# CatCarousel.net
KiCad netlist of a schematic drawn in EAGLE
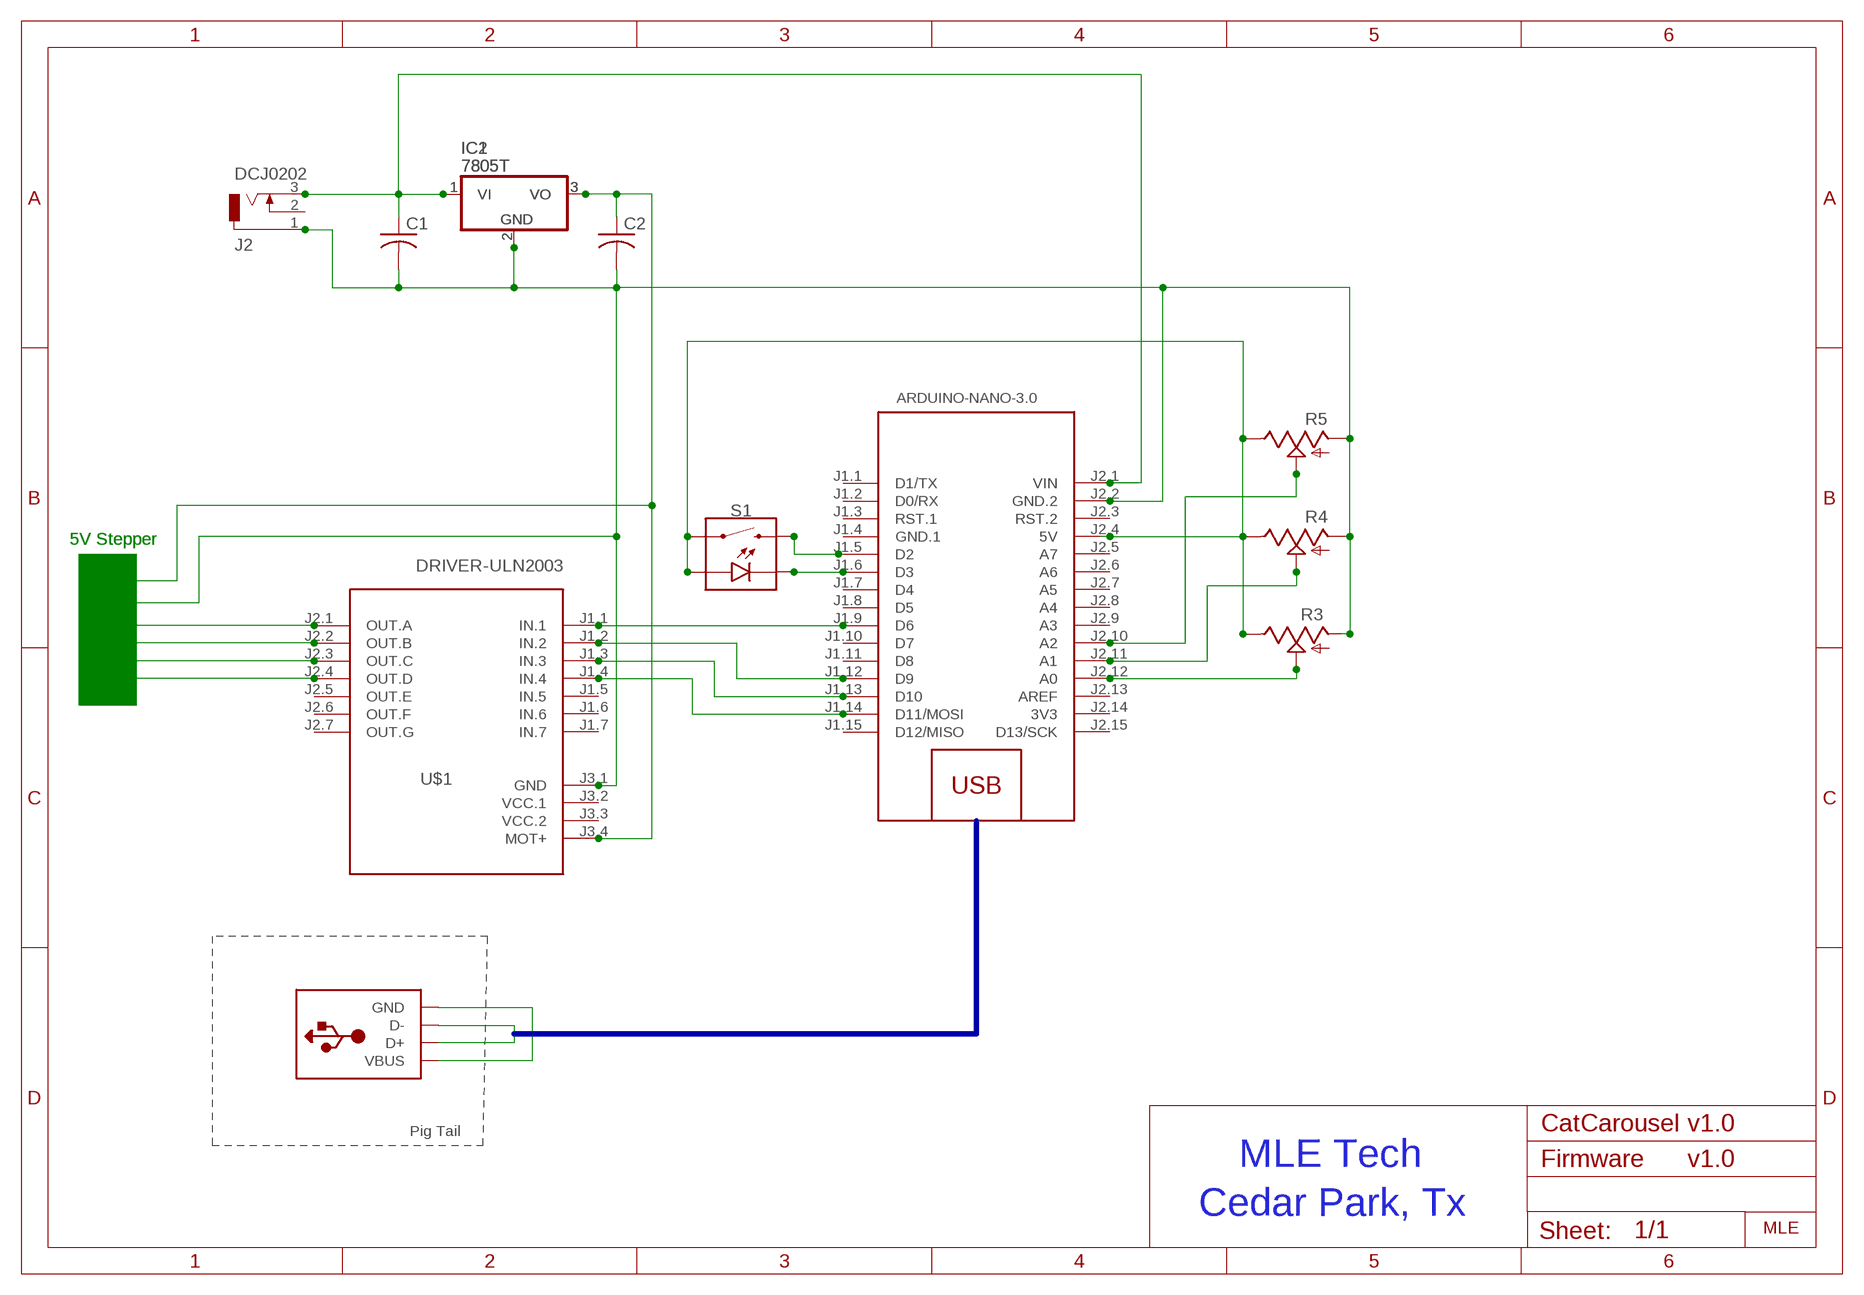
[diagram p0: schematic, sheet 1]

(export (version "E")
  (design (tool "Eeschema 10.0.6"))
  (components
    (comp (ref "C1")
      (value "C-US025-024X044")
      (footprint "eagle-import:C025-024X044")
      (libsource (lib "eagle-import") (part "C-US025-024X044"))
    )
    (comp (ref "C2")
      (value "C-US025-024X044")
      (footprint "eagle-import:C025-024X044")
      (libsource (lib "eagle-import") (part "C-US025-024X044"))
    )
    (comp (ref "IC1")
      (value "7805T")
      (footprint "eagle-import:TO220H")
      (libsource (lib "eagle-import") (part "78T05"))
    )
    (comp (ref "IC2")
      (value "7805T")
      (footprint "eagle-import:TO220H")
      (libsource (lib "eagle-import") (part "78T05"))
    )
    (comp (ref "J2")
      (value "DCJ0202")
      (footprint "eagle-import:DCJ0202")
      (libsource (lib "eagle-import") (part "DCJ0202"))
    )
    (comp (ref "M1")
      (value "ARDUINO-NANO-3.0")
      (footprint "eagle-import:ARDUINO-NANO-3.0")
      (libsource (lib "eagle-import") (part "ARDUINO-NANO-3.0"))
    )
    (comp (ref "R3")
      (value "TRIM_US-CA14H")
      (footprint "eagle-import:CA14H")
      (libsource (lib "eagle-import") (part "TRIM_US-CA14H"))
    )
    (comp (ref "R4")
      (value "TRIM_US-CA14H")
      (footprint "eagle-import:CA14H")
      (libsource (lib "eagle-import") (part "TRIM_US-CA14H"))
    )
    (comp (ref "R5")
      (value "TRIM_US-CA14H")
      (footprint "eagle-import:CA14H")
      (libsource (lib "eagle-import") (part "TRIM_US-CA14H"))
    )
    (comp (ref "S1")
      (value "MOMENTARY-SWITCH-SPST-LED-PTH-12MM")
      (footprint "eagle-import:TACTILE_SWITCH_LED_PTH_12MM")
      (libsource (lib "eagle-import") (part "MOMENTARY-SWITCH-SPST-LED-PTH-12MM"))
    )
    (comp (ref "U$1")
      (value "DRIVER-ULN2003")
      (footprint "eagle-import:DRIVER-ULN2003")
      (libsource (lib "eagle-import") (part "DRIVER-ULN2003"))
    )
    (comp (ref "X2")
      (value "USB-A")
      (footprint "eagle-import:MOLEX_480371000")
      (libsource (lib "eagle-import") (part "USB-A"))
    )
  )
  (nets
    (net (code "1") (name "/3V3") (class "Default")
      (node (ref "M1") (pin "J2.14") (pinfunction "3V3_J2.14") (pintype "power_in"))
    )
    (net (code "2") (name "/GND.1") (class "Default")
      (node (ref "M1") (pin "J1.4") (pinfunction "GND.1_J1.4") (pintype "power_in"))
    )
    (net (code "3") (name "/VCC.1") (class "Default")
      (node (ref "U$1") (pin "J3.2") (pinfunction "VCC.1_J3.2") (pintype "power_in"))
    )
    (net (code "4") (name "Net-(IC1-GND)") (class "Default")
      (node (ref "C1") (pin "2") (pinfunction "2_2") (pintype "passive"))
      (node (ref "C2") (pin "2") (pinfunction "2_2") (pintype "passive"))
      (node (ref "IC1") (pin "2") (pinfunction "GND_2") (pintype "passive"))
      (node (ref "IC2") (pin "2") (pinfunction "GND_2") (pintype "passive"))
      (node (ref "J2") (pin "1") (pinfunction "1_1") (pintype "passive"))
      (node (ref "M1") (pin "J2.2") (pinfunction "GND.2_J2.2") (pintype "power_in"))
      (node (ref "R3") (pin "A") (pinfunction "A_A") (pintype "passive"))
      (node (ref "R4") (pin "A") (pinfunction "A_A") (pintype "passive"))
      (node (ref "R5") (pin "A") (pinfunction "A_A") (pintype "passive"))
      (node (ref "U$1") (pin "J3.1") (pinfunction "GND_J3.1") (pintype "power_in"))
    )
    (net (code "5") (name "Net-(IC1-VI)") (class "Default")
      (node (ref "C1") (pin "1") (pinfunction "1_1") (pintype "passive"))
      (node (ref "IC1") (pin "1") (pinfunction "VI_1") (pintype "input"))
      (node (ref "IC2") (pin "1") (pinfunction "VI_1") (pintype "input"))
      (node (ref "J2") (pin "3") (pinfunction "3_3") (pintype "passive"))
      (node (ref "M1") (pin "J2.1") (pinfunction "VIN_J2.1") (pintype "power_in"))
    )
    (net (code "6") (name "Net-(IC1-VO)") (class "Default")
      (node (ref "C2") (pin "1") (pinfunction "1_1") (pintype "passive"))
      (node (ref "IC1") (pin "3") (pinfunction "VO_3") (pintype "passive"))
      (node (ref "IC2") (pin "3") (pinfunction "VO_3") (pintype "passive"))
      (node (ref "U$1") (pin "J3.4") (pinfunction "MOT+_J3.4") (pintype "bidirectional"))
    )
    (net (code "7") (name "Net-(M1-5V)") (class "Default")
      (node (ref "M1") (pin "J2.4") (pinfunction "5V_J2.4") (pintype "power_in"))
      (node (ref "R3") (pin "E") (pinfunction "E_E") (pintype "passive"))
      (node (ref "R4") (pin "E") (pinfunction "E_E") (pintype "passive"))
      (node (ref "R5") (pin "E") (pinfunction "E_E") (pintype "passive"))
      (node (ref "S1") (pin "4") (pinfunction "1_4") (pintype "passive"))
      (node (ref "S1") (pin "A") (pinfunction "A_A") (pintype "passive"))
    )
    (net (code "8") (name "Net-(M1-A0)") (class "Default")
      (node (ref "M1") (pin "J2.12") (pinfunction "A0_J2.12") (pintype "bidirectional"))
      (node (ref "R3") (pin "S") (pinfunction "S_S") (pintype "passive"))
    )
    (net (code "9") (name "Net-(M1-A1)") (class "Default")
      (node (ref "M1") (pin "J2.11") (pinfunction "A1_J2.11") (pintype "bidirectional"))
      (node (ref "R4") (pin "S") (pinfunction "S_S") (pintype "passive"))
    )
    (net (code "10") (name "Net-(M1-A2)") (class "Default")
      (node (ref "M1") (pin "J2.10") (pinfunction "A2_J2.10") (pintype "bidirectional"))
      (node (ref "R5") (pin "S") (pinfunction "S_S") (pintype "passive"))
    )
    (net (code "11") (name "Net-(M1-D2)") (class "Default")
      (node (ref "M1") (pin "J1.5") (pinfunction "D2_J1.5") (pintype "bidirectional"))
      (node (ref "S1") (pin "2") (pinfunction "2_2") (pintype "passive"))
    )
    (net (code "12") (name "Net-(M1-D3)") (class "Default")
      (node (ref "M1") (pin "J1.6") (pinfunction "D3_J1.6") (pintype "bidirectional"))
      (node (ref "S1") (pin "C") (pinfunction "C_C") (pintype "passive"))
    )
    (net (code "13") (name "Net-(M1-D6)") (class "Default")
      (node (ref "M1") (pin "J1.9") (pinfunction "D6_J1.9") (pintype "bidirectional"))
      (node (ref "U$1") (pin "J1.1") (pinfunction "IN.1_J1.1") (pintype "bidirectional"))
    )
    (net (code "14") (name "Net-(M1-D9)") (class "Default")
      (node (ref "M1") (pin "J1.12") (pinfunction "D9_J1.12") (pintype "bidirectional"))
      (node (ref "U$1") (pin "J1.2") (pinfunction "IN.2_J1.2") (pintype "bidirectional"))
    )
    (net (code "15") (name "Net-(M1-D10)") (class "Default")
      (node (ref "M1") (pin "J1.13") (pinfunction "D10_J1.13") (pintype "bidirectional"))
      (node (ref "U$1") (pin "J1.3") (pinfunction "IN.3_J1.3") (pintype "bidirectional"))
    )
    (net (code "16") (name "Net-(M1-D11{slash}MOSI)") (class "Default")
      (node (ref "M1") (pin "J1.14") (pinfunction "D11/MOSI_J1.14") (pintype "bidirectional"))
      (node (ref "U$1") (pin "J1.4") (pinfunction "IN.4_J1.4") (pintype "bidirectional"))
    )
    (net (code "17") (name "Net-(X2-D+)") (class "Default")
      (node (ref "X2") (pin "2") (pinfunction "D-_2") (pintype "bidirectional"))
      (node (ref "X2") (pin "3") (pinfunction "D+_3") (pintype "bidirectional"))
    )
    (net (code "18") (name "Net-(X2-GND)") (class "Default")
      (node (ref "X2") (pin "1") (pinfunction "VBUS_1") (pintype "power_in"))
      (node (ref "X2") (pin "4") (pinfunction "GND_4") (pintype "power_in"))
    )
    (net (code "19") (name "unconnected-(J2-Pad2)") (class "Default")
      (node (ref "J2") (pin "2") (pinfunction "2_2") (pintype "passive"))
    )
    (net (code "20") (name "unconnected-(M1-A3-PadJ2.9)") (class "Default")
      (node (ref "M1") (pin "J2.9") (pinfunction "A3_J2.9") (pintype "bidirectional"))
    )
    (net (code "21") (name "unconnected-(M1-A4-PadJ2.8)") (class "Default")
      (node (ref "M1") (pin "J2.8") (pinfunction "A4_J2.8") (pintype "bidirectional"))
    )
    (net (code "22") (name "unconnected-(M1-A5-PadJ2.7)") (class "Default")
      (node (ref "M1") (pin "J2.7") (pinfunction "A5_J2.7") (pintype "bidirectional"))
    )
    (net (code "23") (name "unconnected-(M1-A6-PadJ2.6)") (class "Default")
      (node (ref "M1") (pin "J2.6") (pinfunction "A6_J2.6") (pintype "bidirectional"))
    )
    (net (code "24") (name "unconnected-(M1-A7-PadJ2.5)") (class "Default")
      (node (ref "M1") (pin "J2.5") (pinfunction "A7_J2.5") (pintype "bidirectional"))
    )
    (net (code "25") (name "unconnected-(M1-AREF-PadJ2.13)") (class "Default")
      (node (ref "M1") (pin "J2.13") (pinfunction "AREF_J2.13") (pintype "bidirectional"))
    )
    (net (code "26") (name "unconnected-(M1-D0{slash}RX-PadJ1.2)") (class "Default")
      (node (ref "M1") (pin "J1.2") (pinfunction "D0/RX_J1.2") (pintype "bidirectional"))
    )
    (net (code "27") (name "unconnected-(M1-D1{slash}TX-PadJ1.1)") (class "Default")
      (node (ref "M1") (pin "J1.1") (pinfunction "D1/TX_J1.1") (pintype "bidirectional"))
    )
    (net (code "28") (name "unconnected-(M1-D4-PadJ1.7)") (class "Default")
      (node (ref "M1") (pin "J1.7") (pinfunction "D4_J1.7") (pintype "bidirectional"))
    )
    (net (code "29") (name "unconnected-(M1-D5-PadJ1.8)") (class "Default")
      (node (ref "M1") (pin "J1.8") (pinfunction "D5_J1.8") (pintype "bidirectional"))
    )
    (net (code "30") (name "unconnected-(M1-D7-PadJ1.10)") (class "Default")
      (node (ref "M1") (pin "J1.10") (pinfunction "D7_J1.10") (pintype "bidirectional"))
    )
    (net (code "31") (name "unconnected-(M1-D8-PadJ1.11)") (class "Default")
      (node (ref "M1") (pin "J1.11") (pinfunction "D8_J1.11") (pintype "bidirectional"))
    )
    (net (code "32") (name "unconnected-(M1-D12{slash}MISO-PadJ1.15)") (class "Default")
      (node (ref "M1") (pin "J1.15") (pinfunction "D12/MISO_J1.15") (pintype "bidirectional"))
    )
    (net (code "33") (name "unconnected-(M1-D13{slash}SCK-PadJ2.15)") (class "Default")
      (node (ref "M1") (pin "J2.15") (pinfunction "D13/SCK_J2.15") (pintype "bidirectional"))
    )
    (net (code "34") (name "unconnected-(M1-RST.1-PadJ1.3)") (class "Default")
      (node (ref "M1") (pin "J1.3") (pinfunction "RST.1_J1.3") (pintype "bidirectional"))
    )
    (net (code "35") (name "unconnected-(M1-RST.2-PadJ2.3)") (class "Default")
      (node (ref "M1") (pin "J2.3") (pinfunction "RST.2_J2.3") (pintype "bidirectional"))
    )
    (net (code "36") (name "unconnected-(U$1-IN.5-PadJ1.5)") (class "Default")
      (node (ref "U$1") (pin "J1.5") (pinfunction "IN.5_J1.5") (pintype "bidirectional"))
    )
    (net (code "37") (name "unconnected-(U$1-IN.6-PadJ1.6)") (class "Default")
      (node (ref "U$1") (pin "J1.6") (pinfunction "IN.6_J1.6") (pintype "bidirectional"))
    )
    (net (code "38") (name "unconnected-(U$1-IN.7-PadJ1.7)") (class "Default")
      (node (ref "U$1") (pin "J1.7") (pinfunction "IN.7_J1.7") (pintype "bidirectional"))
    )
    (net (code "39") (name "unconnected-(U$1-OUT.A-PadJ2.1)") (class "Default")
      (node (ref "U$1") (pin "J2.1") (pinfunction "OUT.A_J2.1") (pintype "bidirectional"))
    )
    (net (code "40") (name "unconnected-(U$1-OUT.B-PadJ2.2)") (class "Default")
      (node (ref "U$1") (pin "J2.2") (pinfunction "OUT.B_J2.2") (pintype "bidirectional"))
    )
    (net (code "41") (name "unconnected-(U$1-OUT.C-PadJ2.3)") (class "Default")
      (node (ref "U$1") (pin "J2.3") (pinfunction "OUT.C_J2.3") (pintype "bidirectional"))
    )
    (net (code "42") (name "unconnected-(U$1-OUT.D-PadJ2.4)") (class "Default")
      (node (ref "U$1") (pin "J2.4") (pinfunction "OUT.D_J2.4") (pintype "bidirectional"))
    )
    (net (code "43") (name "unconnected-(U$1-OUT.E-PadJ2.5)") (class "Default")
      (node (ref "U$1") (pin "J2.5") (pinfunction "OUT.E_J2.5") (pintype "bidirectional"))
    )
    (net (code "44") (name "unconnected-(U$1-OUT.F-PadJ2.6)") (class "Default")
      (node (ref "U$1") (pin "J2.6") (pinfunction "OUT.F_J2.6") (pintype "bidirectional"))
    )
    (net (code "45") (name "unconnected-(U$1-OUT.G-PadJ2.7)") (class "Default")
      (node (ref "U$1") (pin "J2.7") (pinfunction "OUT.G_J2.7") (pintype "bidirectional"))
    )
    (net (code "46") (name "unconnected-(U$1-VCC.2-PadJ3.3)") (class "Default")
      (node (ref "U$1") (pin "J3.3") (pinfunction "VCC.2_J3.3") (pintype "bidirectional"))
    )
  )
)
